# LORA.net
KiCad netlist of a schematic drawn in Altium Designer
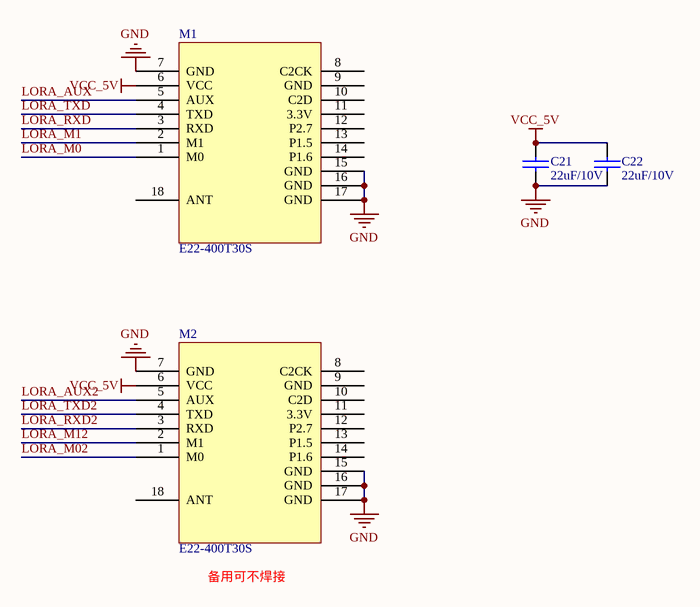
[diagram p0: LORA.SchDoc]

(export (version "E")
  (design (tool "Eeschema 10.0.6"))
  (components
    (comp (ref "C21")
      (value "22uF/10V")
      (footprint "1206C")
      (description "Capacitor")
      (libsource (lib "ZWLIntegrated_Library") (part "CAP"))
    )
    (comp (ref "C22")
      (value "22uF/10V")
      (footprint "1206C")
      (description "Capacitor")
      (libsource (lib "ZWLIntegrated_Library") (part "CAP"))
    )
    (comp (ref "M1")
      (value "E22-400T30S")
      (footprint "E22-400T30S")
      (libsource (lib "stm32") (part "E22-400T30S"))
    )
    (comp (ref "M2")
      (value "E22-400T30S")
      (footprint "E22-400T30S")
      (libsource (lib "stm32") (part "E22-400T30S"))
    )
  )
  (nets
    (net (code "1") (name "/LORA_AUX") (class "Default")
      (node (ref "M1") (pin "5") (pinfunction "AUX_5") (pintype "passive"))
    )
    (net (code "2") (name "/LORA_AUX2") (class "Default")
      (node (ref "M2") (pin "5") (pinfunction "AUX_5") (pintype "passive"))
    )
    (net (code "3") (name "/LORA_M0") (class "Default")
      (node (ref "M1") (pin "1") (pinfunction "M0_1") (pintype "passive"))
    )
    (net (code "4") (name "/LORA_M1") (class "Default")
      (node (ref "M1") (pin "2") (pinfunction "M1_2") (pintype "passive"))
    )
    (net (code "5") (name "/LORA_M02") (class "Default")
      (node (ref "M2") (pin "1") (pinfunction "M0_1") (pintype "passive"))
    )
    (net (code "6") (name "/LORA_M12") (class "Default")
      (node (ref "M2") (pin "2") (pinfunction "M1_2") (pintype "passive"))
    )
    (net (code "7") (name "/LORA_RXD") (class "Default")
      (node (ref "M1") (pin "3") (pinfunction "RXD_3") (pintype "passive"))
    )
    (net (code "8") (name "/LORA_RXD2") (class "Default")
      (node (ref "M2") (pin "3") (pinfunction "RXD_3") (pintype "passive"))
    )
    (net (code "9") (name "/LORA_TXD") (class "Default")
      (node (ref "M1") (pin "4") (pinfunction "TXD_4") (pintype "passive"))
    )
    (net (code "10") (name "/LORA_TXD2") (class "Default")
      (node (ref "M2") (pin "4") (pinfunction "TXD_4") (pintype "passive"))
    )
    (net (code "11") (name "GND") (class "Default")
      (node (ref "C21") (pin "2") (pinfunction "2_2") (pintype "passive"))
      (node (ref "C22") (pin "2") (pinfunction "2_2") (pintype "passive"))
      (node (ref "M1") (pin "15") (pinfunction "GND_15") (pintype "passive"))
      (node (ref "M1") (pin "16") (pinfunction "GND_16") (pintype "passive"))
      (node (ref "M1") (pin "17") (pinfunction "GND_17") (pintype "passive"))
      (node (ref "M1") (pin "7") (pinfunction "GND_7") (pintype "passive"))
      (node (ref "M2") (pin "15") (pinfunction "GND_15") (pintype "passive"))
      (node (ref "M2") (pin "16") (pinfunction "GND_16") (pintype "passive"))
      (node (ref "M2") (pin "17") (pinfunction "GND_17") (pintype "passive"))
      (node (ref "M2") (pin "7") (pinfunction "GND_7") (pintype "passive"))
    )
    (net (code "12") (name "VCC_5V") (class "Default")
      (node (ref "C21") (pin "1") (pinfunction "1_1") (pintype "passive"))
      (node (ref "C22") (pin "1") (pinfunction "1_1") (pintype "passive"))
      (node (ref "M1") (pin "6") (pinfunction "VCC_6") (pintype "passive"))
      (node (ref "M2") (pin "6") (pinfunction "VCC_6") (pintype "passive"))
    )
    (net (code "13") (name "unconnected-(M1-3.3V-Pad11)") (class "Default")
      (node (ref "M1") (pin "11") (pinfunction "3.3V_11") (pintype "passive"))
    )
    (net (code "14") (name "unconnected-(M1-ANT-Pad18)") (class "Default")
      (node (ref "M1") (pin "18") (pinfunction "ANT_18") (pintype "passive"))
    )
    (net (code "15") (name "unconnected-(M1-C2CK-Pad8)") (class "Default")
      (node (ref "M1") (pin "8") (pinfunction "C2CK_8") (pintype "passive"))
    )
    (net (code "16") (name "unconnected-(M1-C2D-Pad10)") (class "Default")
      (node (ref "M1") (pin "10") (pinfunction "C2D_10") (pintype "passive"))
    )
    (net (code "17") (name "unconnected-(M1-GND-Pad9)") (class "Default")
      (node (ref "M1") (pin "9") (pinfunction "GND_9") (pintype "passive"))
    )
    (net (code "18") (name "unconnected-(M1-P1.5-Pad13)") (class "Default")
      (node (ref "M1") (pin "13") (pinfunction "P1.5_13") (pintype "passive"))
    )
    (net (code "19") (name "unconnected-(M1-P1.6-Pad14)") (class "Default")
      (node (ref "M1") (pin "14") (pinfunction "P1.6_14") (pintype "passive"))
    )
    (net (code "20") (name "unconnected-(M1-P2.7-Pad12)") (class "Default")
      (node (ref "M1") (pin "12") (pinfunction "P2.7_12") (pintype "passive"))
    )
    (net (code "21") (name "unconnected-(M2-3.3V-Pad11)") (class "Default")
      (node (ref "M2") (pin "11") (pinfunction "3.3V_11") (pintype "passive"))
    )
    (net (code "22") (name "unconnected-(M2-ANT-Pad18)") (class "Default")
      (node (ref "M2") (pin "18") (pinfunction "ANT_18") (pintype "passive"))
    )
    (net (code "23") (name "unconnected-(M2-C2CK-Pad8)") (class "Default")
      (node (ref "M2") (pin "8") (pinfunction "C2CK_8") (pintype "passive"))
    )
    (net (code "24") (name "unconnected-(M2-C2D-Pad10)") (class "Default")
      (node (ref "M2") (pin "10") (pinfunction "C2D_10") (pintype "passive"))
    )
    (net (code "25") (name "unconnected-(M2-GND-Pad9)") (class "Default")
      (node (ref "M2") (pin "9") (pinfunction "GND_9") (pintype "passive"))
    )
    (net (code "26") (name "unconnected-(M2-P1.5-Pad13)") (class "Default")
      (node (ref "M2") (pin "13") (pinfunction "P1.5_13") (pintype "passive"))
    )
    (net (code "27") (name "unconnected-(M2-P1.6-Pad14)") (class "Default")
      (node (ref "M2") (pin "14") (pinfunction "P1.6_14") (pintype "passive"))
    )
    (net (code "28") (name "unconnected-(M2-P2.7-Pad12)") (class "Default")
      (node (ref "M2") (pin "12") (pinfunction "P2.7_12") (pintype "passive"))
    )
  )
)
